# CarrinhoAcel.net
KiCad netlist of a schematic drawn in EAGLE
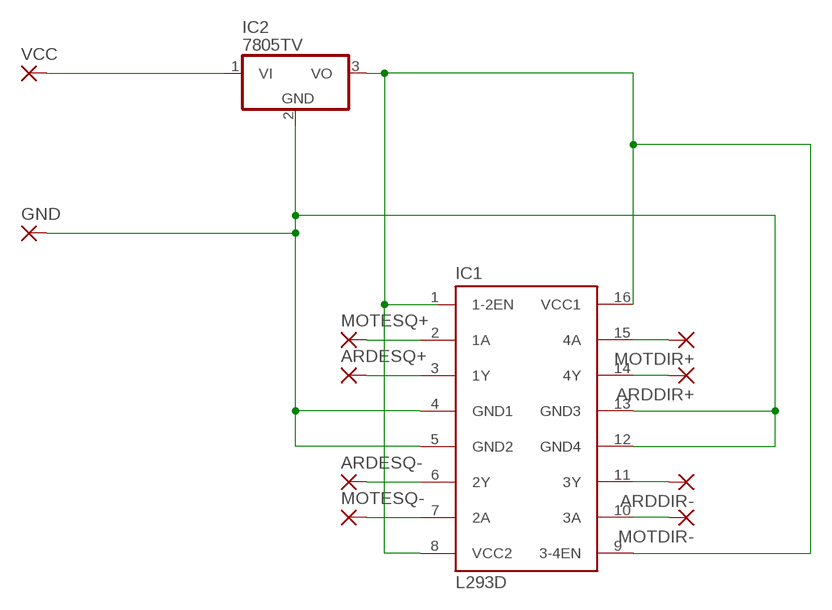
[diagram p0: schematic, sheet 1]

(export (version "E")
  (design (tool "Eeschema 10.0.6"))
  (components
    (comp (ref "ARDDIR+")
      (value "2,15/1,0")
      (footprint "eagle-import:2,15_1,0")
      (libsource (lib "eagle-import") (part "2,15/1,0"))
    )
    (comp (ref "ARDDIR-")
      (value "2,15/1,0")
      (footprint "eagle-import:2,15_1,0")
      (libsource (lib "eagle-import") (part "2,15/1,0"))
    )
    (comp (ref "ARDESQ+")
      (value "2,15/1,0")
      (footprint "eagle-import:2,15_1,0")
      (libsource (lib "eagle-import") (part "2,15/1,0"))
    )
    (comp (ref "ARDESQ-")
      (value "2,15/1,0")
      (footprint "eagle-import:2,15_1,0")
      (libsource (lib "eagle-import") (part "2,15/1,0"))
    )
    (comp (ref "GND")
      (value "2,15/1,0")
      (footprint "eagle-import:2,15_1,0")
      (libsource (lib "eagle-import") (part "2,15/1,0"))
    )
    (comp (ref "IC1")
      (value "L293D")
      (footprint "eagle-import:DIL16")
      (libsource (lib "eagle-import") (part "L293D"))
    )
    (comp (ref "IC2")
      (value "7805TV")
      (footprint "eagle-import:TO220V")
      (libsource (lib "eagle-import") (part "78TV05"))
    )
    (comp (ref "MOTDIR+")
      (value "2,15/1,0")
      (footprint "eagle-import:2,15_1,0")
      (libsource (lib "eagle-import") (part "2,15/1,0"))
    )
    (comp (ref "MOTDIR-")
      (value "2,15/1,0")
      (footprint "eagle-import:2,15_1,0")
      (libsource (lib "eagle-import") (part "2,15/1,0"))
    )
    (comp (ref "MOTESQ+")
      (value "2,15/1,0")
      (footprint "eagle-import:2,15_1,0")
      (libsource (lib "eagle-import") (part "2,15/1,0"))
    )
    (comp (ref "MOTESQ-")
      (value "2,15/1,0")
      (footprint "eagle-import:2,15_1,0")
      (libsource (lib "eagle-import") (part "2,15/1,0"))
    )
    (comp (ref "VCC")
      (value "2,15/1,0")
      (footprint "eagle-import:2,15_1,0")
      (libsource (lib "eagle-import") (part "2,15/1,0"))
    )
  )
  (nets
    (net (code "1") (name "Net-(ARDDIR+-P)") (class "Default")
      (node (ref "ARDDIR+") (pin "1") (pinfunction "P_1") (pintype "passive"))
      (node (ref "IC1") (pin "14") (pinfunction "4Y_14") (pintype "output"))
    )
    (net (code "2") (name "Net-(ARDDIR--P)") (class "Default")
      (node (ref "ARDDIR-") (pin "1") (pinfunction "P_1") (pintype "passive"))
      (node (ref "IC1") (pin "11") (pinfunction "3Y_11") (pintype "output"))
    )
    (net (code "3") (name "Net-(ARDESQ+-P)") (class "Default")
      (node (ref "ARDESQ+") (pin "1") (pinfunction "P_1") (pintype "passive"))
      (node (ref "IC1") (pin "3") (pinfunction "1Y_3") (pintype "output"))
    )
    (net (code "4") (name "Net-(ARDESQ--P)") (class "Default")
      (node (ref "ARDESQ-") (pin "1") (pinfunction "P_1") (pintype "passive"))
      (node (ref "IC1") (pin "6") (pinfunction "2Y_6") (pintype "output"))
    )
    (net (code "5") (name "Net-(GND-P)") (class "Default")
      (node (ref "GND") (pin "1") (pinfunction "P_1") (pintype "passive"))
      (node (ref "IC1") (pin "12") (pinfunction "GND4_12") (pintype "power_in"))
      (node (ref "IC1") (pin "13") (pinfunction "GND3_13") (pintype "power_in"))
      (node (ref "IC1") (pin "4") (pinfunction "GND1_4") (pintype "power_in"))
      (node (ref "IC1") (pin "5") (pinfunction "GND2_5") (pintype "power_in"))
      (node (ref "IC2") (pin "2") (pinfunction "GND_2") (pintype "passive"))
    )
    (net (code "6") (name "Net-(IC1-1A)") (class "Default")
      (node (ref "IC1") (pin "2") (pinfunction "1A_2") (pintype "input"))
      (node (ref "MOTESQ+") (pin "1") (pinfunction "P_1") (pintype "passive"))
    )
    (net (code "7") (name "Net-(IC1-2A)") (class "Default")
      (node (ref "IC1") (pin "7") (pinfunction "2A_7") (pintype "input"))
      (node (ref "MOTESQ-") (pin "1") (pinfunction "P_1") (pintype "passive"))
    )
    (net (code "8") (name "Net-(IC1-3-4EN)") (class "Default")
      (node (ref "IC1") (pin "16") (pinfunction "VCC1_16") (pintype "power_in"))
      (node (ref "IC1") (pin "8") (pinfunction "VCC2_8") (pintype "power_in"))
      (node (ref "IC1") (pin "9") (pinfunction "3-4EN_9") (pintype "input"))
      (node (ref "IC2") (pin "3") (pinfunction "VO_3") (pintype "passive"))
    )
    (net (code "9") (name "Net-(IC1-3A)") (class "Default")
      (node (ref "IC1") (pin "10") (pinfunction "3A_10") (pintype "input"))
      (node (ref "MOTDIR-") (pin "1") (pinfunction "P_1") (pintype "passive"))
    )
    (net (code "10") (name "Net-(IC1-4A)") (class "Default")
      (node (ref "IC1") (pin "15") (pinfunction "4A_15") (pintype "input"))
      (node (ref "MOTDIR+") (pin "1") (pinfunction "P_1") (pintype "passive"))
    )
    (net (code "11") (name "Net-(IC2-VI)") (class "Default")
      (node (ref "IC2") (pin "1") (pinfunction "VI_1") (pintype "input"))
      (node (ref "VCC") (pin "1") (pinfunction "P_1") (pintype "passive"))
    )
    (net (code "12") (name "unconnected-(IC1-1-2EN-Pad1)") (class "Default")
      (node (ref "IC1") (pin "1") (pinfunction "1-2EN_1") (pintype "input"))
    )
  )
)
